# ASL2112.net
KiCad netlist of a schematic drawn in EAGLE
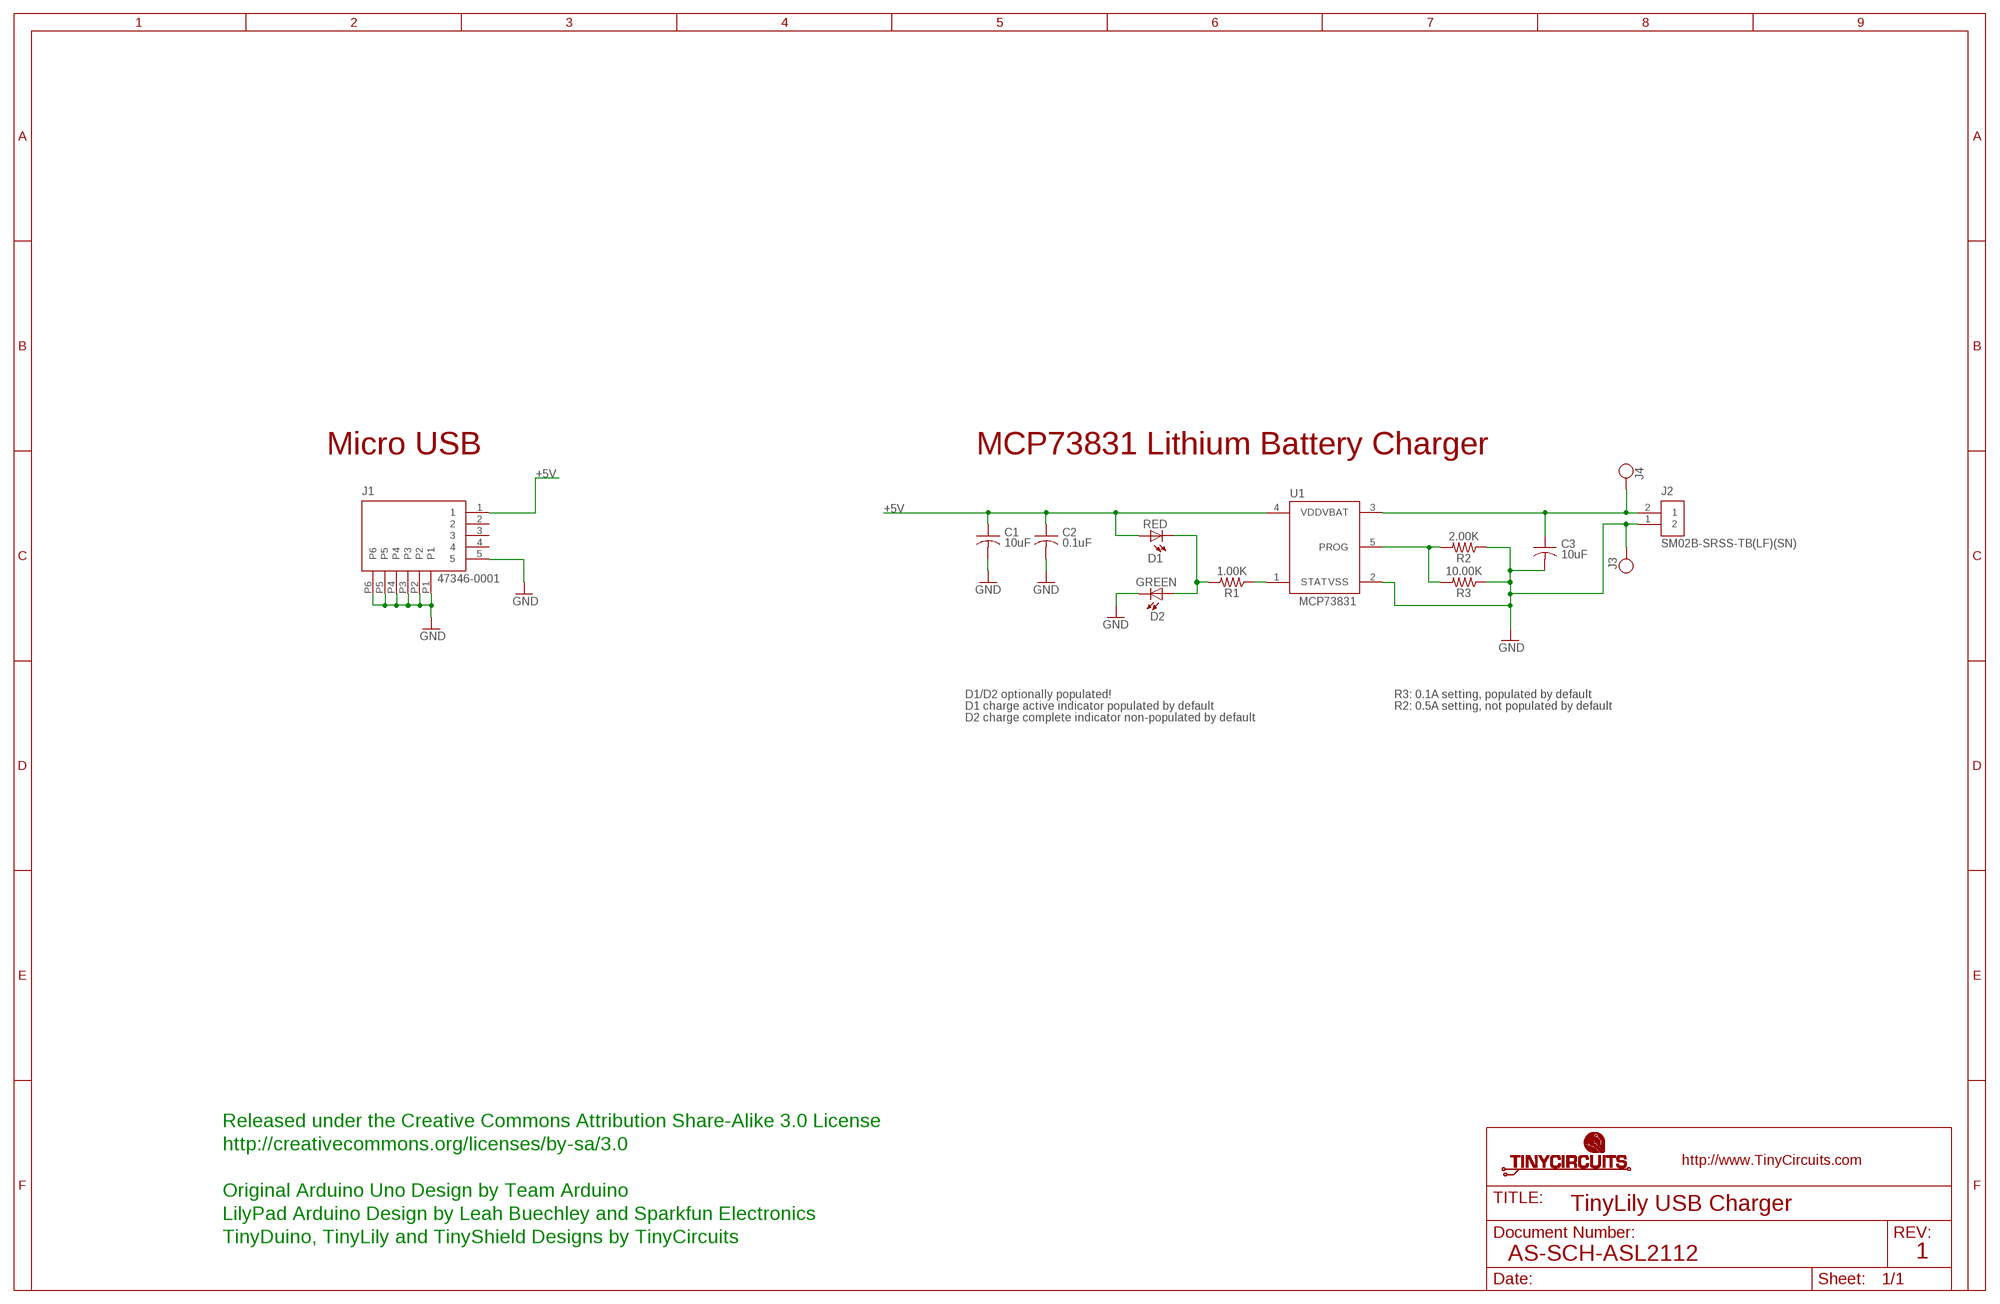
[diagram p0: schematic, sheet 1]

(export (version "E")
  (design (tool "Eeschema 10.0.6"))
  (components
    (comp (ref "C1")
      (value "10uF")
      (footprint "eagle-import:C0603")
      (fields (field (name "PARTNO") "AS-ITM-00002"))
      (libsource (lib "eagle-import") (part "AS-ITM-00002"))
    )
    (comp (ref "C2")
      (value "0.1uF")
      (footprint "eagle-import:C0402")
      (fields (field (name "PARTNO") "AS-ITM-00008"))
      (libsource (lib "eagle-import") (part "AS-ITM-00008"))
    )
    (comp (ref "C3")
      (value "10uF")
      (footprint "eagle-import:C0603")
      (fields (field (name "PARTNO") "AS-ITM-00002") (field (name "PARTNO_1") "AS-ITM-00002"))
      (libsource (lib "eagle-import") (part "AS-ITM-00002"))
    )
    (comp (ref "D1")
      (value "RED")
      (footprint "eagle-import:0402_LED")
      (fields (field (name "PARTNO") "AS-ITM-00057") (field (name "PARTNO_1") "AS-ITM-00057"))
      (libsource (lib "eagle-import") (part "AS-ITM-00057"))
    )
    (comp (ref "D2")
      (value "GREEN")
      (footprint "eagle-import:0402_LED")
      (fields (field (name "PARTNO") "AS-ITM-00038") (field (name "PARTNO_1") "AS-ITM-00038"))
      (libsource (lib "eagle-import") (part "AS-ITM-00038"))
    )
    (comp (ref "J1")
      (value "47346-0001")
      (footprint "eagle-import:MICRO_USB")
      (fields (field (name "PARTNO") "AS-ITM-00021") (field (name "PARTNO_1") "AS-ITM-00021"))
      (libsource (lib "eagle-import") (part "AS-ITM-00021"))
    )
    (comp (ref "J2")
      (value "SM02B-SRSS-TB(LF)(SN)")
      (footprint "eagle-import:JST_SH_2X1")
      (fields (field (name "PARTNO") "AS-ITM-00231"))
      (libsource (lib "eagle-import") (part "AS-ITM-00231"))
    )
    (comp (ref "J3")
      (value "PIN_1X.1\"1")
      (footprint "eagle-import:1X.1__2")
      (libsource (lib "eagle-import") (part "PIN_1X.1{dblquote}1"))
    )
    (comp (ref "J4")
      (value "PIN_1X.1\"1")
      (footprint "eagle-import:1X.1__2")
      (libsource (lib "eagle-import") (part "PIN_1X.1{dblquote}1"))
    )
    (comp (ref "R1")
      (value "1.00K")
      (footprint "eagle-import:0402")
      (fields (field (name "PARTNO") "AS-ITM-00003"))
      (libsource (lib "eagle-import") (part "AS-ITM-00003"))
    )
    (comp (ref "R2")
      (value "2.00K")
      (footprint "eagle-import:0402")
      (fields (field (name "PARTNO") "AS-ITM-00003") (field (name "PARTNO_1") "AS-ITM-00003"))
      (libsource (lib "eagle-import") (part "AS-ITM-00003"))
    )
    (comp (ref "R3")
      (value "10.00K")
      (footprint "eagle-import:0402")
      (fields (field (name "PARTNO") "AS-ITM-00032") (field (name "PARTNO_1") "AS-ITM-00032"))
      (libsource (lib "eagle-import") (part "AS-ITM-00032"))
    )
    (comp (ref "U1")
      (value "MCP73831")
      (footprint "eagle-import:SOT-23")
      (fields (field (name "PARTNO") "AS-ITM-00136"))
      (libsource (lib "eagle-import") (part "AS-ITM-00136"))
    )
  )
  (nets
    (net (code "1") (name "/+5V") (class "Default")
      (node (ref "C1") (pin "1") (pinfunction "1_1") (pintype "passive"))
      (node (ref "C2") (pin "1") (pinfunction "1_1") (pintype "passive"))
      (node (ref "D1") (pin "1") (pinfunction "A_1") (pintype "passive"))
      (node (ref "J1") (pin "1") (pinfunction "1_1") (pintype "bidirectional"))
      (node (ref "U1") (pin "4") (pinfunction "VDD_4") (pintype "bidirectional"))
    )
    (net (code "2") (name "GND") (class "Default")
      (node (ref "C1") (pin "2") (pinfunction "2_2") (pintype "passive"))
      (node (ref "C2") (pin "2") (pinfunction "2_2") (pintype "passive"))
      (node (ref "C3") (pin "2") (pinfunction "2_2") (pintype "passive"))
      (node (ref "D2") (pin "2") (pinfunction "C_2") (pintype "passive"))
      (node (ref "J1") (pin "5") (pinfunction "5_5") (pintype "bidirectional"))
      (node (ref "J1") (pin "P1") (pinfunction "P1_P1") (pintype "bidirectional"))
      (node (ref "J1") (pin "P2") (pinfunction "P2_P2") (pintype "bidirectional"))
      (node (ref "J1") (pin "P3") (pinfunction "P3_P3") (pintype "bidirectional"))
      (node (ref "J1") (pin "P4") (pinfunction "P4_P4") (pintype "bidirectional"))
      (node (ref "J1") (pin "P5") (pinfunction "P5_P5") (pintype "bidirectional"))
      (node (ref "J1") (pin "P6") (pinfunction "P6_P6") (pintype "bidirectional"))
      (node (ref "J2") (pin "1") (pinfunction "2_1") (pintype "bidirectional"))
      (node (ref "J3") (pin "1") (pinfunction "1_1") (pintype "bidirectional"))
      (node (ref "R2") (pin "1") (pinfunction "1_1") (pintype "passive"))
      (node (ref "R3") (pin "1") (pinfunction "1_1") (pintype "passive"))
      (node (ref "U1") (pin "2") (pinfunction "VSS_2") (pintype "bidirectional"))
    )
    (net (code "3") (name "Net-(D1-C)") (class "Default")
      (node (ref "D1") (pin "2") (pinfunction "C_2") (pintype "passive"))
      (node (ref "D2") (pin "1") (pinfunction "A_1") (pintype "passive"))
      (node (ref "R1") (pin "2") (pinfunction "2_2") (pintype "passive"))
    )
    (net (code "4") (name "Net-(J2-1)") (class "Default")
      (node (ref "C3") (pin "1") (pinfunction "1_1") (pintype "passive"))
      (node (ref "J2") (pin "2") (pinfunction "1_2") (pintype "bidirectional"))
      (node (ref "J4") (pin "1") (pinfunction "1_1") (pintype "bidirectional"))
      (node (ref "U1") (pin "3") (pinfunction "VBAT_3") (pintype "bidirectional"))
    )
    (net (code "5") (name "Net-(U1-PROG)") (class "Default")
      (node (ref "R2") (pin "2") (pinfunction "2_2") (pintype "passive"))
      (node (ref "R3") (pin "2") (pinfunction "2_2") (pintype "passive"))
      (node (ref "U1") (pin "5") (pinfunction "PROG_5") (pintype "bidirectional"))
    )
    (net (code "6") (name "Net-(U1-STAT)") (class "Default")
      (node (ref "R1") (pin "1") (pinfunction "1_1") (pintype "passive"))
      (node (ref "U1") (pin "1") (pinfunction "STAT_1") (pintype "bidirectional"))
    )
    (net (code "7") (name "unconnected-(J1-Pad2)") (class "Default")
      (node (ref "J1") (pin "2") (pinfunction "2_2") (pintype "bidirectional"))
    )
    (net (code "8") (name "unconnected-(J1-Pad3)") (class "Default")
      (node (ref "J1") (pin "3") (pinfunction "3_3") (pintype "bidirectional"))
    )
    (net (code "9") (name "unconnected-(J1-Pad4)") (class "Default")
      (node (ref "J1") (pin "4") (pinfunction "4_4") (pintype "bidirectional"))
    )
  )
)
